# Power_Board1.net
KiCad netlist of a schematic drawn in Altium Designer
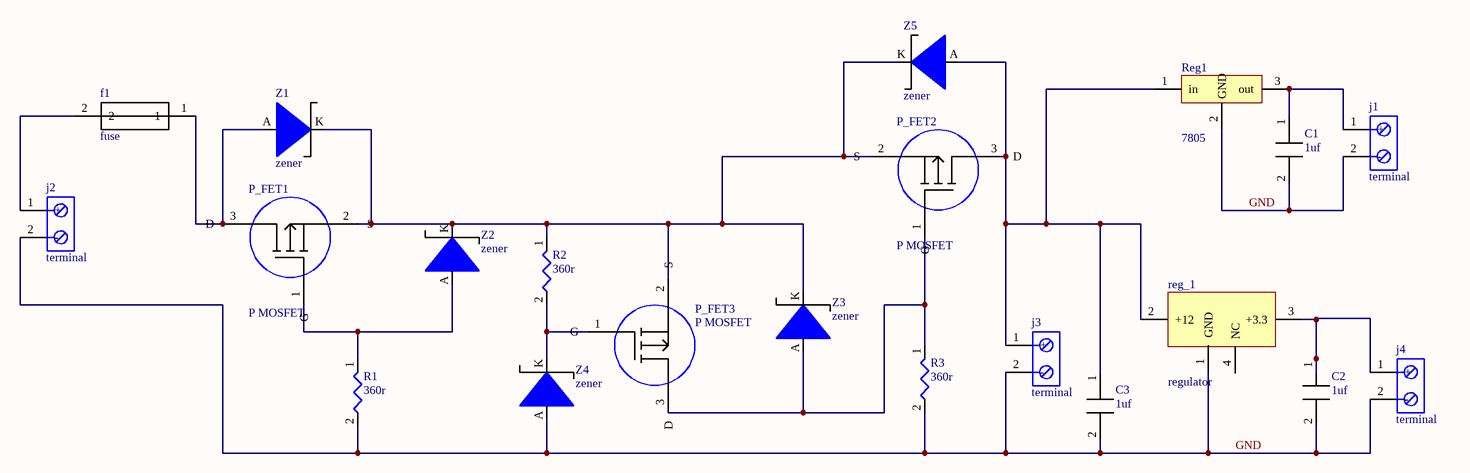
[diagram p0: Power Board1.SchDoc]

(export (version "E")
  (design (tool "Eeschema 10.0.6"))
  (components
    (comp (ref "C1")
      (value "1uf")
      (footprint "Capacitor")
      (description "Aluminum Electrolytic Capacitor, Aluminum (wet)")
      (fields
        (field (name "MANUFACTURER") "Wurth Electronics")
        (field (name "MANUFACTURER PART NUMBER") "860020672005")
      )
      (libsource (lib "Integrated_Library1") (part "capacitor"))
    )
    (comp (ref "C2")
      (value "1uf")
      (footprint "Capacitor")
      (description "Aluminum Electrolytic Capacitor, Aluminum (wet)")
      (fields
        (field (name "MANUFACTURER") "Wurth Electronics")
        (field (name "MANUFACTURER PART NUMBER") "860020672005")
      )
      (libsource (lib "Integrated_Library1") (part "capacitor"))
    )
    (comp (ref "C3")
      (value "1uf")
      (footprint "Capacitor")
      (description "Aluminum Electrolytic Capacitor, Aluminum (wet)")
      (fields
        (field (name "MANUFACTURER") "Wurth Electronics")
        (field (name "MANUFACTURER PART NUMBER") "860020672005")
      )
      (libsource (lib "Integrated_Library1") (part "capacitor"))
    )
    (comp (ref "f1")
      (value "fuse")
      (footprint "Fuse")
      (description "Electric Fuse, Fast Blow, 1A, 32VAC, 63VDC, 35A (IR), Surface Mount, 0603")
      (fields (field (name "MANUFACTURER") "Bel") (field (name "MANUFACTURER PART NUMBER") "0686F1000-01"))
      (libsource (lib "Integrated_Library1") (part "Fuse"))
    )
    (comp (ref "j1")
      (value "terminal")
      (footprint "TERMINAL")
      (description "Barrier Strip Terminal Block")
      (fields
        (field (name "MANUFACTURER") "Wurth Electronics")
        (field (name "MANUFACTURER PART NUMBER") "691137710002")
      )
      (libsource (lib "my schematics") (part "terminal"))
    )
    (comp (ref "j2")
      (value "terminal")
      (footprint "TERMINAL")
      (description "Barrier Strip Terminal Block")
      (fields
        (field (name "MANUFACTURER") "Wurth Electronics")
        (field (name "MANUFACTURER PART NUMBER") "691137710002")
      )
      (libsource (lib "my schematics") (part "terminal"))
    )
    (comp (ref "j3")
      (value "terminal")
      (footprint "TERMINAL")
      (description "Barrier Strip Terminal Block")
      (fields
        (field (name "MANUFACTURER") "Wurth Electronics")
        (field (name "MANUFACTURER PART NUMBER") "691137710002")
      )
      (libsource (lib "my schematics") (part "terminal"))
    )
    (comp (ref "j4")
      (value "terminal")
      (footprint "TERMINAL")
      (description "Barrier Strip Terminal Block")
      (fields
        (field (name "MANUFACTURER") "Wurth Electronics")
        (field (name "MANUFACTURER PART NUMBER") "691137710002")
      )
      (libsource (lib "my schematics") (part "terminal"))
    )
    (comp (ref "P_FET1")
      (value "P MOSFET")
      (footprint "P-MOSFET")
      (description "Trans MOSFET P-CH 50V 0.18A Automotive AEC-Q101 3-Pin SOT-23 T/R")
      (fields
        (field (name "MANUFACTURER") "Nexperia")
        (field (name "MANUFACTURER PART NUMBER") "BSS84AK,215")
      )
      (libsource (lib "Integrated_Library1") (part "P_MOSFET"))
    )
    (comp (ref "P_FET2")
      (value "P MOSFET")
      (footprint "P-MOSFET")
      (description "Trans MOSFET P-CH 50V 0.18A Automotive AEC-Q101 3-Pin SOT-23 T/R")
      (fields
        (field (name "MANUFACTURER") "Nexperia")
        (field (name "MANUFACTURER PART NUMBER") "BSS84AK,215")
      )
      (libsource (lib "Integrated_Library1") (part "P_MOSFET"))
    )
    (comp (ref "P_FET3")
      (value "P MOSFET")
      (footprint "P-MOSFET")
      (description "Trans MOSFET P-CH 50V 0.18A Automotive AEC-Q101 3-Pin SOT-23 T/R")
      (fields
        (field (name "MANUFACTURER") "Nexperia")
        (field (name "MANUFACTURER PART NUMBER") "BSS84AK,215")
      )
      (libsource (lib "Integrated_Library1") (part "P_MOSFET"))
    )
    (comp (ref "R1")
      (value "360r")
      (footprint "R0805")
      (fields
        (field (name "MANUFACTURER") "Vishay")
        (field (name "MANUFACTURER PART NUMBER") "CRCW0805360RFKEA")
        (field (name "TOLERANCE") "1%")
      )
      (libsource (lib "Integrated_Library1") (part "resistor"))
    )
    (comp (ref "R2")
      (value "360r")
      (footprint "R0805")
      (fields
        (field (name "MANUFACTURER") "Vishay")
        (field (name "MANUFACTURER PART NUMBER") "CRCW0805360RFKEA")
        (field (name "TOLERANCE") "1%")
      )
      (libsource (lib "Integrated_Library1") (part "resistor"))
    )
    (comp (ref "R3")
      (value "360r")
      (footprint "R0805")
      (fields
        (field (name "MANUFACTURER") "Vishay")
        (field (name "MANUFACTURER PART NUMBER") "CRCW0805360RFKEA")
        (field (name "TOLERANCE") "1%")
      )
      (libsource (lib "Integrated_Library1") (part "resistor"))
    )
    (comp (ref "Reg1")
      (value "7805")
      (footprint "7805")
      (description "Fixed Positive Standard Regulator, 5VBIPolar, PSFM3")
      (fields
        (field (name "MANUFACTURER") "STMicroelectronics")
        (field (name "MANUFACTURER PART NUMBER") "L7805C-V")
      )
      (libsource (lib "Integrated_Library1") (part "7805"))
    )
    (comp (ref "reg_1")
      (value "regulator")
      (footprint "reg_3V3")
      (description "Fixed Positive LDO Regulator, 3.3V, 1V Dropout, CMOS, PDSO4")
      (fields
        (field (name "MANUFACTURER") "ON Semiconductor")
        (field (name "MANUFACTURER PART NUMBER") "NCP553SQ33T1G")
      )
      (libsource (lib "Integrated_Library1") (part "12v-3.3v"))
    )
    (comp (ref "Z1")
      (value "zener")
      (footprint "zeber")
      (description "Zener Diode, 12V V(Z), 5.39%, 0.37W, Silicon, Unidirectional")
      (fields
        (field (name "MANUFACTURER") "Diodes")
        (field (name "MANUFACTURER PART NUMBER") "BZT52C12-13-F")
      )
      (libsource (lib "Integrated_Library1") (part "zener diode"))
    )
    (comp (ref "Z2")
      (value "zener")
      (footprint "zeber")
      (description "Zener Diode, 12V V(Z), 5.39%, 0.37W, Silicon, Unidirectional")
      (fields
        (field (name "MANUFACTURER") "Diodes")
        (field (name "MANUFACTURER PART NUMBER") "BZT52C12-13-F")
      )
      (libsource (lib "Integrated_Library1") (part "zener diode"))
    )
    (comp (ref "Z3")
      (value "zener")
      (footprint "zeber")
      (description "Zener Diode, 12V V(Z), 5.39%, 0.37W, Silicon, Unidirectional")
      (fields
        (field (name "MANUFACTURER") "Diodes")
        (field (name "MANUFACTURER PART NUMBER") "BZT52C12-13-F")
      )
      (libsource (lib "Integrated_Library1") (part "zener diode"))
    )
    (comp (ref "Z4")
      (value "zener")
      (footprint "zeber")
      (description "Zener Diode, 12V V(Z), 5.39%, 0.37W, Silicon, Unidirectional")
      (fields
        (field (name "MANUFACTURER") "Diodes")
        (field (name "MANUFACTURER PART NUMBER") "BZT52C12-13-F")
      )
      (libsource (lib "Integrated_Library1") (part "zener diode"))
    )
    (comp (ref "Z5")
      (value "zener")
      (footprint "zeber")
      (description "Zener Diode, 12V V(Z), 5.39%, 0.37W, Silicon, Unidirectional")
      (fields
        (field (name "MANUFACTURER") "Diodes")
        (field (name "MANUFACTURER PART NUMBER") "BZT52C12-13-F")
      )
      (libsource (lib "Integrated_Library1") (part "zener diode"))
    )
  )
  (nets
    (net (code "1") (name "/GND") (class "Default")
      (node (ref "C1") (pin "2") (pinfunction "33_2") (pintype "passive"))
      (node (ref "C2") (pin "2") (pinfunction "33_2") (pintype "passive"))
      (node (ref "C3") (pin "2") (pinfunction "33_2") (pintype "passive"))
      (node (ref "R1") (pin "2") (pinfunction "2_2") (pintype "passive"))
      (node (ref "R3") (pin "2") (pinfunction "2_2") (pintype "passive"))
      (node (ref "Reg1") (pin "2") (pinfunction "GND_2") (pintype "passive"))
      (node (ref "Z4") (pin "A") (pinfunction "24_A") (pintype "passive"))
      (node (ref "j1") (pin "2") (pinfunction "-_2") (pintype "passive"))
      (node (ref "j2") (pin "2") (pinfunction "-_2") (pintype "passive"))
      (node (ref "j3") (pin "2") (pinfunction "-_2") (pintype "passive"))
      (node (ref "j4") (pin "2") (pinfunction "-_2") (pintype "passive"))
      (node (ref "reg_1") (pin "1") (pinfunction "GND_1") (pintype "passive"))
    )
    (net (code "2") (name "Net-(C1-34)") (class "Default")
      (node (ref "C1") (pin "1") (pinfunction "34_1") (pintype "passive"))
      (node (ref "Reg1") (pin "3") (pinfunction "out_3") (pintype "passive"))
      (node (ref "j1") (pin "1") (pinfunction "+_1") (pintype "passive"))
    )
    (net (code "3") (name "Net-(C2-34)") (class "Default")
      (node (ref "C2") (pin "1") (pinfunction "34_1") (pintype "passive"))
      (node (ref "j4") (pin "1") (pinfunction "+_1") (pintype "passive"))
      (node (ref "reg_1") (pin "3") (pinfunction "+3.3_3") (pintype "passive"))
    )
    (net (code "4") (name "Net-(C3-34)") (class "Default")
      (node (ref "C3") (pin "1") (pinfunction "34_1") (pintype "passive"))
      (node (ref "P_FET2") (pin "3") (pinfunction "D_3") (pintype "passive"))
      (node (ref "Reg1") (pin "1") (pinfunction "in_1") (pintype "passive"))
      (node (ref "Z5") (pin "A") (pinfunction "24_A") (pintype "passive"))
      (node (ref "j3") (pin "1") (pinfunction "+_1") (pintype "passive"))
      (node (ref "reg_1") (pin "2") (pinfunction "+12_2") (pintype "passive"))
    )
    (net (code "5") (name "Net-(P_FET1-D)") (class "Default")
      (node (ref "P_FET1") (pin "3") (pinfunction "D_3") (pintype "passive"))
      (node (ref "Z1") (pin "A") (pinfunction "24_A") (pintype "passive"))
      (node (ref "f1") (pin "1") (pinfunction "1_1") (pintype "passive"))
    )
    (net (code "6") (name "Net-(P_FET1-G)") (class "Default")
      (node (ref "P_FET1") (pin "1") (pinfunction "G_1") (pintype "passive"))
      (node (ref "R1") (pin "1") (pinfunction "1_1") (pintype "passive"))
      (node (ref "Z2") (pin "A") (pinfunction "24_A") (pintype "passive"))
    )
    (net (code "7") (name "Net-(P_FET1-S)") (class "Default")
      (node (ref "P_FET1") (pin "2") (pinfunction "S_2") (pintype "passive"))
      (node (ref "P_FET2") (pin "2") (pinfunction "S_2") (pintype "passive"))
      (node (ref "P_FET3") (pin "2") (pinfunction "S_2") (pintype "passive"))
      (node (ref "R2") (pin "1") (pinfunction "1_1") (pintype "passive"))
      (node (ref "Z1") (pin "K") (pinfunction "23_K") (pintype "passive"))
      (node (ref "Z2") (pin "K") (pinfunction "23_K") (pintype "passive"))
      (node (ref "Z3") (pin "K") (pinfunction "23_K") (pintype "passive"))
      (node (ref "Z5") (pin "K") (pinfunction "23_K") (pintype "passive"))
    )
    (net (code "8") (name "Net-(P_FET2-G)") (class "Default")
      (node (ref "P_FET2") (pin "1") (pinfunction "G_1") (pintype "passive"))
      (node (ref "P_FET3") (pin "3") (pinfunction "D_3") (pintype "passive"))
      (node (ref "R3") (pin "1") (pinfunction "1_1") (pintype "passive"))
      (node (ref "Z3") (pin "A") (pinfunction "24_A") (pintype "passive"))
    )
    (net (code "9") (name "Net-(P_FET3-G)") (class "Default")
      (node (ref "P_FET3") (pin "1") (pinfunction "G_1") (pintype "passive"))
      (node (ref "R2") (pin "2") (pinfunction "2_2") (pintype "passive"))
      (node (ref "Z4") (pin "K") (pinfunction "23_K") (pintype "passive"))
    )
    (net (code "10") (name "Net-(j2-+)") (class "Default")
      (node (ref "f1") (pin "2") (pinfunction "2_2") (pintype "passive"))
      (node (ref "j2") (pin "1") (pinfunction "+_1") (pintype "passive"))
    )
    (net (code "11") (name "unconnected-(reg_1-NC-Pad4)") (class "Default")
      (node (ref "reg_1") (pin "4") (pinfunction "NC_4") (pintype "passive"))
    )
  )
)
